# conn_usbc.net
KiCad netlist of a schematic drawn in Altium Designer
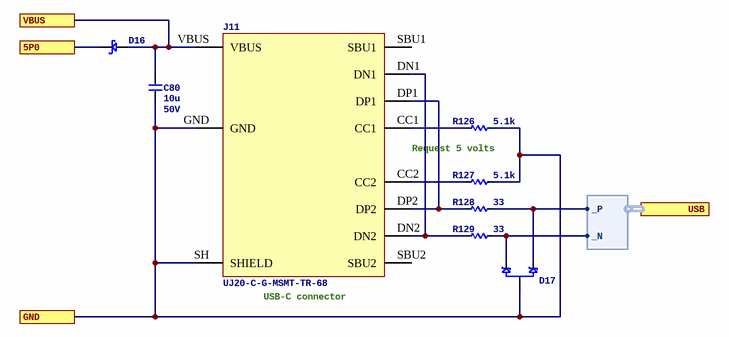
[diagram p0: conn_usbc.SchDoc]

(export (version "E")
  (design (tool "Eeschema 10.0.6"))
  (components
    (comp (ref "C80")
      (value "CL31B106KBHNNNE")
      (footprint "C1206")
      (fields
        (field (name "CAPACITANCE") "10u")
        (field (name "MANUFACTURER") "Samsung Electro-Mechanics")
        (field (name "VOLTAGE RATING") "50V")
      )
      (libsource (lib "database") (part "__template_cap"))
    )
    (comp (ref "D16")
      (value "MSS2P2-M3/89A")
      (footprint "ESMP")
      (description "DIODE SCHOTTKY 20V 2A MICROSMP")
      (fields (field (name "MANUFACTURER") "Vishay Semiconductor Diodes Division"))
      (libsource (lib "SSCP") (part "SCHOTTKY_MSS2P2-M3/89A"))
    )
    (comp (ref "D17")
      (value "PESD2USB3UX")
      (footprint "3SOT23")
      (description "DIODE ESD USB SOT-23")
      (fields (field (name "MANUFACTURER") "Nexperia USA Inc."))
      (libsource (lib "SSCP") (part "TVS_PESD2USB3UX-T"))
    )
    (comp (ref "J11")
      (value "UJ20-C-G-MSMT-TR-68")
      (footprint "CONN_USBC_UJ20-C-G-MSMT-TR-68")
      (fields (field (name "MANUFACTURER") "Same Sky"))
      (libsource (lib "SSCP") (part "CONN_USBC_UJ20-C-G-MSMT-TR-68"))
    )
    (comp (ref "R126")
      (value "5.1k")
      (footprint "R0402")
      (fields
        (field (name "TOLERANCE") "1%")
        (field (name "MANUFACTURER PART NUMBER") "0402WGF5101TCE")
        (field (name "MANUFACTURER") "UNI-ROYAL(Uniroyal Elec)")
      )
      (libsource (lib "database") (part "__template_resistor"))
    )
    (comp (ref "R127")
      (value "5.1k")
      (footprint "R0402")
      (fields
        (field (name "TOLERANCE") "1%")
        (field (name "MANUFACTURER PART NUMBER") "0402WGF5101TCE")
        (field (name "MANUFACTURER") "UNI-ROYAL(Uniroyal Elec)")
      )
      (libsource (lib "database") (part "__template_resistor"))
    )
    (comp (ref "R128")
      (value "33")
      (footprint "R0402")
      (fields
        (field (name "TOLERANCE") "1%")
        (field (name "MANUFACTURER PART NUMBER") "0402WGF330JTCE")
        (field (name "MANUFACTURER") "UNI-ROYAL(Uniroyal Elec)")
      )
      (libsource (lib "database") (part "__template_resistor"))
    )
    (comp (ref "R129")
      (value "33")
      (footprint "R0402")
      (fields
        (field (name "TOLERANCE") "1%")
        (field (name "MANUFACTURER PART NUMBER") "0402WGF330JTCE")
        (field (name "MANUFACTURER") "UNI-ROYAL(Uniroyal Elec)")
      )
      (libsource (lib "database") (part "__template_resistor"))
    )
  )
  (nets
    (net (code "2") (name "/5P0") (class "Default") (node (ref "D16") (pin "1") (pintype "passive")))
    (net (code "3") (name "/GND") (class "Default")
      (node (ref "C80") (pin "2") (pintype "passive"))
      (node (ref "D17") (pin "3") (pintype "passive"))
      (node (ref "J11") (pin "GND") (pinfunction "GND_GND") (pintype "power_in"))
      (node (ref "J11") (pin "SH") (pinfunction "SHIELD_SH") (pintype "power_in"))
      (node (ref "R126") (pin "1") (pintype "passive"))
      (node (ref "R127") (pin "1") (pintype "passive"))
    )
    (net (code "4") (name "/VBUS") (class "Default")
      (node (ref "C80") (pin "1") (pintype "passive"))
      (node (ref "D16") (pin "2") (pintype "passive"))
      (node (ref "J11") (pin "VBUS") (pinfunction "VBUS_VBUS") (pintype "passive"))
    )
    (net (code "6") (name "Net-(D17-Pad1)") (class "Default")
      (node (ref "D17") (pin "1") (pintype "passive"))
      (node (ref "R129") (pin "1") (pintype "passive"))
    )
    (net (code "7") (name "Net-(D17-Pad2)") (class "Default")
      (node (ref "D17") (pin "2") (pintype "passive"))
      (node (ref "R128") (pin "1") (pintype "passive"))
    )
    (net (code "8") (name "Net-(J11-PadCC1)") (class "Default")
      (node (ref "J11") (pin "CC1") (pinfunction "CC1_CC1") (pintype "passive"))
      (node (ref "R126") (pin "2") (pintype "passive"))
    )
    (net (code "9") (name "Net-(J11-PadCC2)") (class "Default")
      (node (ref "J11") (pin "CC2") (pinfunction "CC2_CC2") (pintype "passive"))
      (node (ref "R127") (pin "2") (pintype "passive"))
    )
    (net (code "10") (name "Net-(J11-PadDN1)") (class "Default")
      (node (ref "J11") (pin "DN1") (pinfunction "DN1_DN1") (pintype "passive"))
      (node (ref "J11") (pin "DN2") (pinfunction "DN2_DN2") (pintype "passive"))
      (node (ref "R129") (pin "2") (pintype "passive"))
    )
    (net (code "11") (name "Net-(J11-PadDP1)") (class "Default")
      (node (ref "J11") (pin "DP1") (pinfunction "DP1_DP1") (pintype "passive"))
      (node (ref "J11") (pin "DP2") (pinfunction "DP2_DP2") (pintype "passive"))
      (node (ref "R128") (pin "2") (pintype "passive"))
    )
    (net (code "12") (name "unconnected-(J11-PadSBU1)") (class "Default")
      (node (ref "J11") (pin "SBU1") (pinfunction "SBU1_SBU1") (pintype "passive"))
    )
    (net (code "13") (name "unconnected-(J11-PadSBU2)") (class "Default")
      (node (ref "J11") (pin "SBU2") (pinfunction "SBU2_SBU2") (pintype "passive"))
    )
  )
)
